# tda7266-7x7w.net
KiCad netlist of a schematic drawn in EAGLE
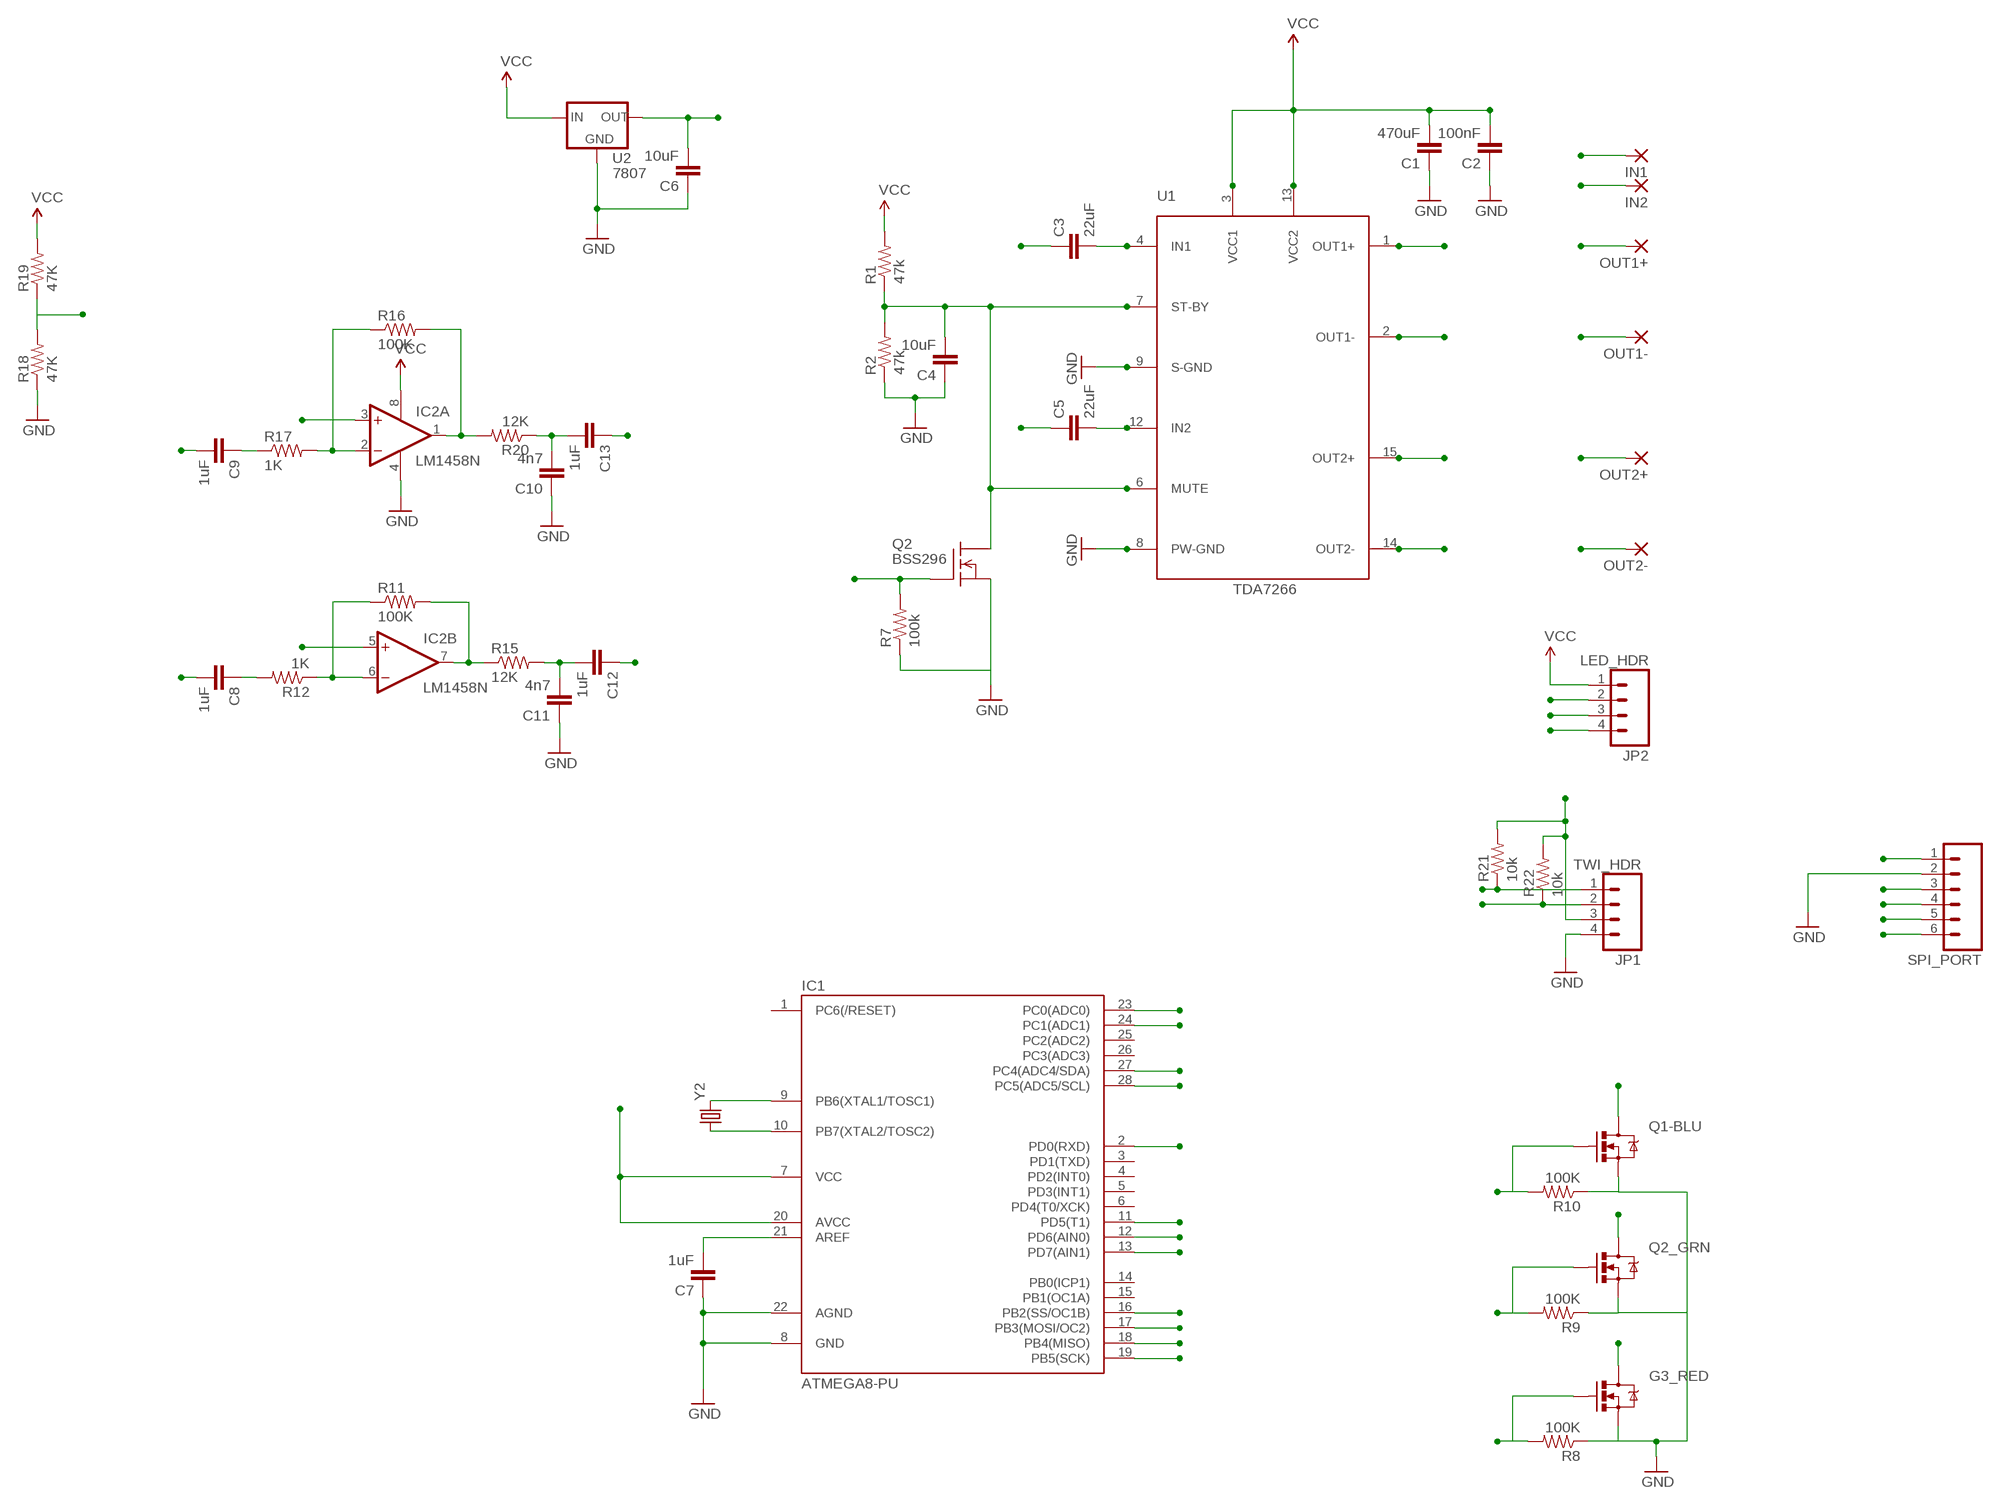
[diagram p0: schematic, sheet 1]

(export (version "E")
  (design (tool "Eeschema 10.0.6"))
  (components
    (comp (ref "C1")
      (value "470uF")
      (footprint "eagle-import:CAP-PTH-SMALL")
      (libsource (lib "eagle-import") (part "CAPPTH"))
    )
    (comp (ref "C2")
      (value "100nF")
      (footprint "eagle-import:CAP-PTH-SMALL")
      (libsource (lib "eagle-import") (part "CAPPTH"))
    )
    (comp (ref "C3")
      (value "22uF")
      (footprint "eagle-import:CAP-PTH-SMALL")
      (libsource (lib "eagle-import") (part "CAPPTH"))
    )
    (comp (ref "C4")
      (value "10uF")
      (footprint "eagle-import:CAP-PTH-SMALL")
      (libsource (lib "eagle-import") (part "CAPPTH"))
    )
    (comp (ref "C5")
      (value "22uF")
      (footprint "eagle-import:CAP-PTH-SMALL")
      (libsource (lib "eagle-import") (part "CAPPTH"))
    )
    (comp (ref "C6")
      (value "10uF")
      (footprint "eagle-import:CAP-PTH-SMALL")
      (libsource (lib "eagle-import") (part "CAPPTH"))
    )
    (comp (ref "C7")
      (value "1uF")
      (footprint "eagle-import:CAP-PTH-SMALL")
      (libsource (lib "eagle-import") (part "CAPPTH"))
    )
    (comp (ref "C8")
      (value "1uF")
      (footprint "eagle-import:CAP-PTH-SMALL")
      (libsource (lib "eagle-import") (part "CAPPTH"))
    )
    (comp (ref "C9")
      (value "1uF")
      (footprint "eagle-import:CAP-PTH-SMALL")
      (libsource (lib "eagle-import") (part "CAPPTH"))
    )
    (comp (ref "C10")
      (value "4n7")
      (footprint "eagle-import:CAP-PTH-SMALL")
      (libsource (lib "eagle-import") (part "CAPPTH"))
    )
    (comp (ref "C11")
      (value "4n7")
      (footprint "eagle-import:CAP-PTH-SMALL")
      (libsource (lib "eagle-import") (part "CAPPTH"))
    )
    (comp (ref "C12")
      (value "1uF")
      (footprint "eagle-import:CAP-PTH-SMALL")
      (libsource (lib "eagle-import") (part "CAPPTH"))
    )
    (comp (ref "C13")
      (value "1uF")
      (footprint "eagle-import:CAP-PTH-SMALL")
      (libsource (lib "eagle-import") (part "CAPPTH"))
    )
    (comp (ref "G3_RED")
      (value "MOSFET-NCHANNELPTH2")
      (footprint "eagle-import:TO220V")
      (libsource (lib "eagle-import") (part "MOSFET-NCHANNELPTH2"))
    )
    (comp (ref "IC1")
      (value "ATMEGA8-PU")
      (footprint "eagle-import:DIL28-3")
      (libsource (lib "eagle-import") (part "ATMEGA8-PU"))
    )
    (comp (ref "IC2")
      (value "LM1458N")
      (footprint "eagle-import:DIL08")
      (libsource (lib "eagle-import") (part "1458NLM"))
    )
    (comp (ref "IN1")
      (value "2,54/0,8")
      (footprint "eagle-import:2,54_0,8")
      (libsource (lib "eagle-import") (part "2,54/0,8"))
    )
    (comp (ref "IN2")
      (value "2,54/0,8")
      (footprint "eagle-import:2,54_0,8")
      (libsource (lib "eagle-import") (part "2,54/0,8"))
    )
    (comp (ref "JP1")
      (value "TWI_HDR")
      (footprint "eagle-import:1X04_LONGPADS")
      (libsource (lib "eagle-import") (part "M04LONGPADS"))
    )
    (comp (ref "JP2")
      (value "LED_HDR")
      (footprint "eagle-import:1X04_LONGPADS")
      (libsource (lib "eagle-import") (part "M04LONGPADS"))
    )
    (comp (ref "OUT1+")
      (value "2,54/0,8")
      (footprint "eagle-import:2,54_0,8")
      (libsource (lib "eagle-import") (part "2,54/0,8"))
    )
    (comp (ref "OUT1-")
      (value "2,54/0,8")
      (footprint "eagle-import:2,54_0,8")
      (libsource (lib "eagle-import") (part "2,54/0,8"))
    )
    (comp (ref "OUT2+")
      (value "2,54/0,8")
      (footprint "eagle-import:2,54_0,8")
      (libsource (lib "eagle-import") (part "2,54/0,8"))
    )
    (comp (ref "OUT2-")
      (value "2,54/0,8")
      (footprint "eagle-import:2,54_0,8")
      (libsource (lib "eagle-import") (part "2,54/0,8"))
    )
    (comp (ref "Q1-BLU")
      (value "MOSFET-NCHANNELPTH2")
      (footprint "eagle-import:TO220V")
      (libsource (lib "eagle-import") (part "MOSFET-NCHANNELPTH2"))
    )
    (comp (ref "Q2")
      (value "BSS296")
      (footprint "eagle-import:TO92")
      (libsource (lib "eagle-import") (part "BSS296"))
    )
    (comp (ref "Q2_GRN")
      (value "MOSFET-NCHANNELPTH2")
      (footprint "eagle-import:TO220V")
      (libsource (lib "eagle-import") (part "MOSFET-NCHANNELPTH2"))
    )
    (comp (ref "R1")
      (value "47k")
      (footprint "eagle-import:1_6W-RES")
      (libsource (lib "eagle-import") (part "RESISTORPTH-1/6W"))
    )
    (comp (ref "R2")
      (value "47k")
      (footprint "eagle-import:1_6W-RES")
      (libsource (lib "eagle-import") (part "RESISTORPTH-1/6W"))
    )
    (comp (ref "R7")
      (value "100k")
      (footprint "eagle-import:1_6W-RES")
      (libsource (lib "eagle-import") (part "RESISTORPTH-1/6W"))
    )
    (comp (ref "R8")
      (value "100K")
      (footprint "eagle-import:1_6W-RES")
      (libsource (lib "eagle-import") (part "RESISTORPTH-1/6W"))
    )
    (comp (ref "R9")
      (value "100K")
      (footprint "eagle-import:1_6W-RES")
      (libsource (lib "eagle-import") (part "RESISTORPTH-1/6W"))
    )
    (comp (ref "R10")
      (value "100K")
      (footprint "eagle-import:1_6W-RES")
      (libsource (lib "eagle-import") (part "RESISTORPTH-1/6W"))
    )
    (comp (ref "R11")
      (value "100K")
      (footprint "eagle-import:1_6W-RES")
      (libsource (lib "eagle-import") (part "RESISTORPTH-1/6W"))
    )
    (comp (ref "R12")
      (value "1K")
      (footprint "eagle-import:1_6W-RES")
      (libsource (lib "eagle-import") (part "RESISTORPTH-1/6W"))
    )
    (comp (ref "R15")
      (value "12K")
      (footprint "eagle-import:1_6W-RES")
      (libsource (lib "eagle-import") (part "RESISTORPTH-1/6W"))
    )
    (comp (ref "R16")
      (value "100K")
      (footprint "eagle-import:1_6W-RES")
      (libsource (lib "eagle-import") (part "RESISTORPTH-1/6W"))
    )
    (comp (ref "R17")
      (value "1K")
      (footprint "eagle-import:1_6W-RES")
      (libsource (lib "eagle-import") (part "RESISTORPTH-1/6W"))
    )
    (comp (ref "R18")
      (value "47K")
      (footprint "eagle-import:1_6W-RES")
      (libsource (lib "eagle-import") (part "RESISTORPTH-1/6W"))
    )
    (comp (ref "R19")
      (value "47K")
      (footprint "eagle-import:1_6W-RES")
      (libsource (lib "eagle-import") (part "RESISTORPTH-1/6W"))
    )
    (comp (ref "R20")
      (value "12K")
      (footprint "eagle-import:1_6W-RES")
      (libsource (lib "eagle-import") (part "RESISTORPTH-1/6W"))
    )
    (comp (ref "R21")
      (value "10k")
      (footprint "eagle-import:1_6W-RES")
      (libsource (lib "eagle-import") (part "RESISTORPTH-1/6W"))
    )
    (comp (ref "R22")
      (value "10k")
      (footprint "eagle-import:1_6W-RES")
      (libsource (lib "eagle-import") (part "RESISTORPTH-1/6W"))
    )
    (comp (ref "SPI_PORT")
      (value "M06LONGPADS")
      (footprint "eagle-import:1X06_LONGPADS")
      (libsource (lib "eagle-import") (part "M06LONGPADS"))
    )
    (comp (ref "U1")
      (value "TDA7266")
      (footprint "eagle-import:MULTIWATT-15")
      (libsource (lib "eagle-import") (part "TDA7266TDA7266-MW15"))
    )
    (comp (ref "U2")
      (value "7807")
      (footprint "eagle-import:TO220-IGO")
      (libsource (lib "eagle-import") (part "V_REG_78XXSINK"))
    )
    (comp (ref "Y2")
      (value "CRYSTALHC49US")
      (footprint "eagle-import:HC49US")
      (libsource (lib "eagle-import") (part "CRYSTALHC49US"))
    )
  )
  (nets
    (net (code "1") (name "/5V") (class "Default")
      (node (ref "C6") (pin "2") (pinfunction "2_2") (pintype "passive"))
      (node (ref "IC1") (pin "20") (pinfunction "AVCC_20") (pintype "passive"))
      (node (ref "IC1") (pin "7") (pinfunction "VCC_7") (pintype "power_in"))
      (node (ref "JP1") (pin "3") (pinfunction "3_3") (pintype "passive"))
      (node (ref "R21") (pin "2") (pinfunction "2_2") (pintype "passive"))
      (node (ref "R22") (pin "2") (pinfunction "2_2") (pintype "passive"))
      (node (ref "SPI_PORT") (pin "1") (pinfunction "1_1") (pintype "passive"))
      (node (ref "U2") (pin "OUT") (pinfunction "OUT_OUT") (pintype "output"))
    )
    (net (code "2") (name "/AUDIO_1") (class "Default")
      (node (ref "C13") (pin "1") (pinfunction "1_1") (pintype "passive"))
      (node (ref "IC1") (pin "23") (pinfunction "PC0(ADC0)_23") (pintype "bidirectional"))
    )
    (net (code "3") (name "/AUDIO_2") (class "Default")
      (node (ref "C12") (pin "1") (pinfunction "1_1") (pintype "passive"))
      (node (ref "IC1") (pin "24") (pinfunction "PC1(ADC1)_24") (pintype "bidirectional"))
    )
    (net (code "4") (name "/AUD_CTRL") (class "Default")
      (node (ref "IC1") (pin "2") (pinfunction "PD0(RXD)_2") (pintype "bidirectional"))
      (node (ref "Q2") (pin "1") (pinfunction "G_1") (pintype "passive"))
      (node (ref "R7") (pin "2") (pinfunction "2_2") (pintype "passive"))
    )
    (net (code "5") (name "/BLU") (class "Default")
      (node (ref "IC1") (pin "13") (pinfunction "PD7(AIN1)_13") (pintype "bidirectional"))
      (node (ref "Q1-BLU") (pin "1") (pinfunction "G_1") (pintype "passive"))
      (node (ref "R10") (pin "2") (pinfunction "2_2") (pintype "passive"))
    )
    (net (code "6") (name "/BLU_OUT") (class "Default")
      (node (ref "JP2") (pin "4") (pinfunction "4_4") (pintype "passive"))
      (node (ref "Q1-BLU") (pin "2") (pinfunction "D_2") (pintype "passive"))
    )
    (net (code "7") (name "/GRN") (class "Default")
      (node (ref "IC1") (pin "12") (pinfunction "PD6(AIN0)_12") (pintype "bidirectional"))
      (node (ref "Q2_GRN") (pin "1") (pinfunction "G_1") (pintype "passive"))
      (node (ref "R9") (pin "2") (pinfunction "2_2") (pintype "passive"))
    )
    (net (code "8") (name "/GRN_OUT") (class "Default")
      (node (ref "JP2") (pin "3") (pinfunction "3_3") (pintype "passive"))
      (node (ref "Q2_GRN") (pin "2") (pinfunction "D_2") (pintype "passive"))
    )
    (net (code "9") (name "/IN1") (class "Default")
      (node (ref "C3") (pin "1") (pinfunction "1_1") (pintype "passive"))
      (node (ref "C8") (pin "2") (pinfunction "2_2") (pintype "passive"))
      (node (ref "IN1") (pin "1") (pinfunction "P_1") (pintype "passive"))
    )
    (net (code "10") (name "/IN2") (class "Default")
      (node (ref "C5") (pin "1") (pinfunction "1_1") (pintype "passive"))
      (node (ref "C9") (pin "2") (pinfunction "2_2") (pintype "passive"))
      (node (ref "IN2") (pin "1") (pinfunction "P_1") (pintype "passive"))
    )
    (net (code "11") (name "/MISO") (class "Default")
      (node (ref "IC1") (pin "18") (pinfunction "PB4(MISO)_18") (pintype "bidirectional"))
      (node (ref "SPI_PORT") (pin "4") (pinfunction "4_4") (pintype "passive"))
    )
    (net (code "12") (name "/MOSI") (class "Default")
      (node (ref "IC1") (pin "17") (pinfunction "PB3(MOSI/OC2)_17") (pintype "bidirectional"))
      (node (ref "SPI_PORT") (pin "5") (pinfunction "5_5") (pintype "passive"))
    )
    (net (code "13") (name "/OUT1+") (class "Default")
      (node (ref "OUT1+") (pin "1") (pinfunction "P_1") (pintype "passive"))
      (node (ref "U1") (pin "1") (pinfunction "OUT1+_1") (pintype "bidirectional"))
    )
    (net (code "14") (name "/OUT1-") (class "Default")
      (node (ref "OUT1-") (pin "1") (pinfunction "P_1") (pintype "passive"))
      (node (ref "U1") (pin "2") (pinfunction "OUT1-_2") (pintype "bidirectional"))
    )
    (net (code "15") (name "/OUT2+") (class "Default")
      (node (ref "OUT2+") (pin "1") (pinfunction "P_1") (pintype "passive"))
      (node (ref "U1") (pin "15") (pinfunction "OUT2+_15") (pintype "bidirectional"))
    )
    (net (code "16") (name "/OUT2-") (class "Default")
      (node (ref "OUT2-") (pin "1") (pinfunction "P_1") (pintype "passive"))
      (node (ref "U1") (pin "14") (pinfunction "OUT2-_14") (pintype "bidirectional"))
    )
    (net (code "17") (name "/RED") (class "Default")
      (node (ref "G3_RED") (pin "1") (pinfunction "G_1") (pintype "passive"))
      (node (ref "IC1") (pin "11") (pinfunction "PD5(T1)_11") (pintype "bidirectional"))
      (node (ref "R8") (pin "2") (pinfunction "2_2") (pintype "passive"))
    )
    (net (code "18") (name "/RED_OUT") (class "Default")
      (node (ref "G3_RED") (pin "2") (pinfunction "D_2") (pintype "passive"))
      (node (ref "JP2") (pin "2") (pinfunction "2_2") (pintype "passive"))
    )
    (net (code "19") (name "/SCL") (class "Default")
      (node (ref "IC1") (pin "28") (pinfunction "PC5(ADC5/SCL)_28") (pintype "bidirectional"))
      (node (ref "JP1") (pin "2") (pinfunction "2_2") (pintype "passive"))
      (node (ref "R22") (pin "1") (pinfunction "1_1") (pintype "passive"))
    )
    (net (code "20") (name "/SDA") (class "Default")
      (node (ref "IC1") (pin "27") (pinfunction "PC4(ADC4/SDA)_27") (pintype "bidirectional"))
      (node (ref "JP1") (pin "1") (pinfunction "1_1") (pintype "passive"))
      (node (ref "R21") (pin "1") (pinfunction "1_1") (pintype "passive"))
    )
    (net (code "21") (name "/V_DIV") (class "Default")
      (node (ref "IC2") (pin "3") (pinfunction "+IN_3") (pintype "input"))
      (node (ref "IC2") (pin "5") (pinfunction "+IN_5") (pintype "input"))
      (node (ref "R18") (pin "2") (pinfunction "2_2") (pintype "passive"))
      (node (ref "R19") (pin "1") (pinfunction "1_1") (pintype "passive"))
    )
    (net (code "22") (name "/{slash}SCK") (class "Default")
      (node (ref "IC1") (pin "19") (pinfunction "PB5(SCK)_19") (pintype "bidirectional"))
      (node (ref "SPI_PORT") (pin "3") (pinfunction "3_3") (pintype "passive"))
    )
    (net (code "23") (name "/{slash}SS") (class "Default")
      (node (ref "IC1") (pin "16") (pinfunction "PB2(SS/OC1B)_16") (pintype "bidirectional"))
      (node (ref "SPI_PORT") (pin "6") (pinfunction "6_6") (pintype "passive"))
    )
    (net (code "24") (name "GND") (class "Default")
      (node (ref "C1") (pin "1") (pinfunction "1_1") (pintype "passive"))
      (node (ref "C10") (pin "1") (pinfunction "1_1") (pintype "passive"))
      (node (ref "C11") (pin "1") (pinfunction "1_1") (pintype "passive"))
      (node (ref "C2") (pin "1") (pinfunction "1_1") (pintype "passive"))
      (node (ref "C4") (pin "1") (pinfunction "1_1") (pintype "passive"))
      (node (ref "C6") (pin "1") (pinfunction "1_1") (pintype "passive"))
      (node (ref "C7") (pin "1") (pinfunction "1_1") (pintype "passive"))
      (node (ref "G3_RED") (pin "3") (pinfunction "S_3") (pintype "passive"))
      (node (ref "IC1") (pin "22") (pinfunction "AGND_22") (pintype "power_in"))
      (node (ref "IC1") (pin "8") (pinfunction "GND_8") (pintype "power_in"))
      (node (ref "IC2") (pin "4") (pinfunction "V-_4") (pintype "power_in"))
      (node (ref "JP1") (pin "4") (pinfunction "4_4") (pintype "passive"))
      (node (ref "Q1-BLU") (pin "3") (pinfunction "S_3") (pintype "passive"))
      (node (ref "Q2") (pin "3") (pinfunction "S_3") (pintype "passive"))
      (node (ref "Q2_GRN") (pin "3") (pinfunction "S_3") (pintype "passive"))
      (node (ref "R10") (pin "1") (pinfunction "1_1") (pintype "passive"))
      (node (ref "R18") (pin "1") (pinfunction "1_1") (pintype "passive"))
      (node (ref "R2") (pin "1") (pinfunction "1_1") (pintype "passive"))
      (node (ref "R7") (pin "1") (pinfunction "1_1") (pintype "passive"))
      (node (ref "R8") (pin "1") (pinfunction "1_1") (pintype "passive"))
      (node (ref "R9") (pin "1") (pinfunction "1_1") (pintype "passive"))
      (node (ref "SPI_PORT") (pin "2") (pinfunction "2_2") (pintype "passive"))
      (node (ref "U1") (pin "8") (pinfunction "PW-GND_8") (pintype "bidirectional"))
      (node (ref "U1") (pin "9") (pinfunction "S-GND_9") (pintype "bidirectional"))
      (node (ref "U2") (pin "GND") (pinfunction "GND_GND") (pintype "input"))
    )
    (net (code "25") (name "Net-(C8-Pad1)") (class "Default")
      (node (ref "C8") (pin "1") (pinfunction "1_1") (pintype "passive"))
      (node (ref "R12") (pin "2") (pinfunction "2_2") (pintype "passive"))
    )
    (net (code "26") (name "Net-(C9-Pad1)") (class "Default")
      (node (ref "C9") (pin "1") (pinfunction "1_1") (pintype "passive"))
      (node (ref "R17") (pin "1") (pinfunction "1_1") (pintype "passive"))
    )
    (net (code "27") (name "Net-(C10-Pad2)") (class "Default")
      (node (ref "C10") (pin "2") (pinfunction "2_2") (pintype "passive"))
      (node (ref "C13") (pin "2") (pinfunction "2_2") (pintype "passive"))
      (node (ref "R20") (pin "1") (pinfunction "1_1") (pintype "passive"))
    )
    (net (code "28") (name "Net-(C11-Pad2)") (class "Default")
      (node (ref "C11") (pin "2") (pinfunction "2_2") (pintype "passive"))
      (node (ref "C12") (pin "2") (pinfunction "2_2") (pintype "passive"))
      (node (ref "R15") (pin "2") (pinfunction "2_2") (pintype "passive"))
    )
    (net (code "29") (name "Net-(IC1-AREF)") (class "Default")
      (node (ref "C7") (pin "2") (pinfunction "2_2") (pintype "passive"))
      (node (ref "IC1") (pin "21") (pinfunction "AREF_21") (pintype "passive"))
    )
    (net (code "30") (name "Net-(IC1-PB6(XTAL1{slash}TOSC1))") (class "Default")
      (node (ref "IC1") (pin "9") (pinfunction "PB6(XTAL1/TOSC1)_9") (pintype "bidirectional"))
      (node (ref "Y2") (pin "2") (pinfunction "2_2") (pintype "passive"))
    )
    (net (code "31") (name "Net-(IC1-PB7(XTAL2{slash}TOSC2))") (class "Default")
      (node (ref "IC1") (pin "10") (pinfunction "PB7(XTAL2/TOSC2)_10") (pintype "bidirectional"))
      (node (ref "Y2") (pin "1") (pinfunction "1_1") (pintype "passive"))
    )
    (net (code "32") (name "Net-(IC2A--IN)") (class "Default")
      (node (ref "IC2") (pin "2") (pinfunction "-IN_2") (pintype "input"))
      (node (ref "R16") (pin "1") (pinfunction "1_1") (pintype "passive"))
      (node (ref "R17") (pin "2") (pinfunction "2_2") (pintype "passive"))
    )
    (net (code "33") (name "Net-(IC2A-OUT)") (class "Default")
      (node (ref "IC2") (pin "1") (pinfunction "OUT_1") (pintype "output"))
      (node (ref "R16") (pin "2") (pinfunction "2_2") (pintype "passive"))
      (node (ref "R20") (pin "2") (pinfunction "2_2") (pintype "passive"))
    )
    (net (code "34") (name "Net-(IC2B--IN)") (class "Default")
      (node (ref "IC2") (pin "6") (pinfunction "-IN_6") (pintype "input"))
      (node (ref "R11") (pin "1") (pinfunction "1_1") (pintype "passive"))
      (node (ref "R12") (pin "1") (pinfunction "1_1") (pintype "passive"))
    )
    (net (code "35") (name "Net-(IC2B-OUT)") (class "Default")
      (node (ref "IC2") (pin "7") (pinfunction "OUT_7") (pintype "output"))
      (node (ref "R11") (pin "2") (pinfunction "2_2") (pintype "passive"))
      (node (ref "R15") (pin "1") (pinfunction "1_1") (pintype "passive"))
    )
    (net (code "36") (name "Net-(Q2-D)") (class "Default")
      (node (ref "C4") (pin "2") (pinfunction "2_2") (pintype "passive"))
      (node (ref "Q2") (pin "2") (pinfunction "D_2") (pintype "passive"))
      (node (ref "R1") (pin "1") (pinfunction "1_1") (pintype "passive"))
      (node (ref "R2") (pin "2") (pinfunction "2_2") (pintype "passive"))
      (node (ref "U1") (pin "6") (pinfunction "MUTE_6") (pintype "bidirectional"))
      (node (ref "U1") (pin "7") (pinfunction "ST-BY_7") (pintype "bidirectional"))
    )
    (net (code "37") (name "Net-(U1-IN1)") (class "Default")
      (node (ref "C3") (pin "2") (pinfunction "2_2") (pintype "passive"))
      (node (ref "U1") (pin "4") (pinfunction "IN1_4") (pintype "bidirectional"))
    )
    (net (code "38") (name "Net-(U1-IN2)") (class "Default")
      (node (ref "C5") (pin "2") (pinfunction "2_2") (pintype "passive"))
      (node (ref "U1") (pin "12") (pinfunction "IN2_12") (pintype "bidirectional"))
    )
    (net (code "39") (name "VCC") (class "Default")
      (node (ref "C1") (pin "2") (pinfunction "2_2") (pintype "passive"))
      (node (ref "C2") (pin "2") (pinfunction "2_2") (pintype "passive"))
      (node (ref "IC2") (pin "8") (pinfunction "V+_8") (pintype "power_in"))
      (node (ref "JP2") (pin "1") (pinfunction "1_1") (pintype "passive"))
      (node (ref "R1") (pin "2") (pinfunction "2_2") (pintype "passive"))
      (node (ref "R19") (pin "2") (pinfunction "2_2") (pintype "passive"))
      (node (ref "U1") (pin "13") (pinfunction "VCC2_13") (pintype "bidirectional"))
      (node (ref "U1") (pin "3") (pinfunction "VCC1_3") (pintype "bidirectional"))
      (node (ref "U2") (pin "IN") (pinfunction "IN_IN") (pintype "input"))
    )
    (net (code "40") (name "unconnected-(IC1-PB0(ICP1)-Pad14)") (class "Default")
      (node (ref "IC1") (pin "14") (pinfunction "PB0(ICP1)_14") (pintype "bidirectional"))
    )
    (net (code "41") (name "unconnected-(IC1-PB1(OC1A)-Pad15)") (class "Default")
      (node (ref "IC1") (pin "15") (pinfunction "PB1(OC1A)_15") (pintype "bidirectional"))
    )
    (net (code "42") (name "unconnected-(IC1-PC2(ADC2)-Pad25)") (class "Default")
      (node (ref "IC1") (pin "25") (pinfunction "PC2(ADC2)_25") (pintype "bidirectional"))
    )
    (net (code "43") (name "unconnected-(IC1-PC3(ADC3)-Pad26)") (class "Default")
      (node (ref "IC1") (pin "26") (pinfunction "PC3(ADC3)_26") (pintype "bidirectional"))
    )
    (net (code "44") (name "unconnected-(IC1-PC6({slash}RESET)-Pad1)") (class "Default")
      (node (ref "IC1") (pin "1") (pinfunction "PC6(/RESET)_1") (pintype "bidirectional"))
    )
    (net (code "45") (name "unconnected-(IC1-PD1(TXD)-Pad3)") (class "Default")
      (node (ref "IC1") (pin "3") (pinfunction "PD1(TXD)_3") (pintype "bidirectional"))
    )
    (net (code "46") (name "unconnected-(IC1-PD2(INT0)-Pad4)") (class "Default")
      (node (ref "IC1") (pin "4") (pinfunction "PD2(INT0)_4") (pintype "bidirectional"))
    )
    (net (code "47") (name "unconnected-(IC1-PD3(INT1)-Pad5)") (class "Default")
      (node (ref "IC1") (pin "5") (pinfunction "PD3(INT1)_5") (pintype "bidirectional"))
    )
    (net (code "48") (name "unconnected-(IC1-PD4(T0{slash}XCK)-Pad6)") (class "Default")
      (node (ref "IC1") (pin "6") (pinfunction "PD4(T0/XCK)_6") (pintype "bidirectional"))
    )
  )
)
